# Load_Bank_Master.net
KiCad netlist of a schematic drawn in Altium Designer
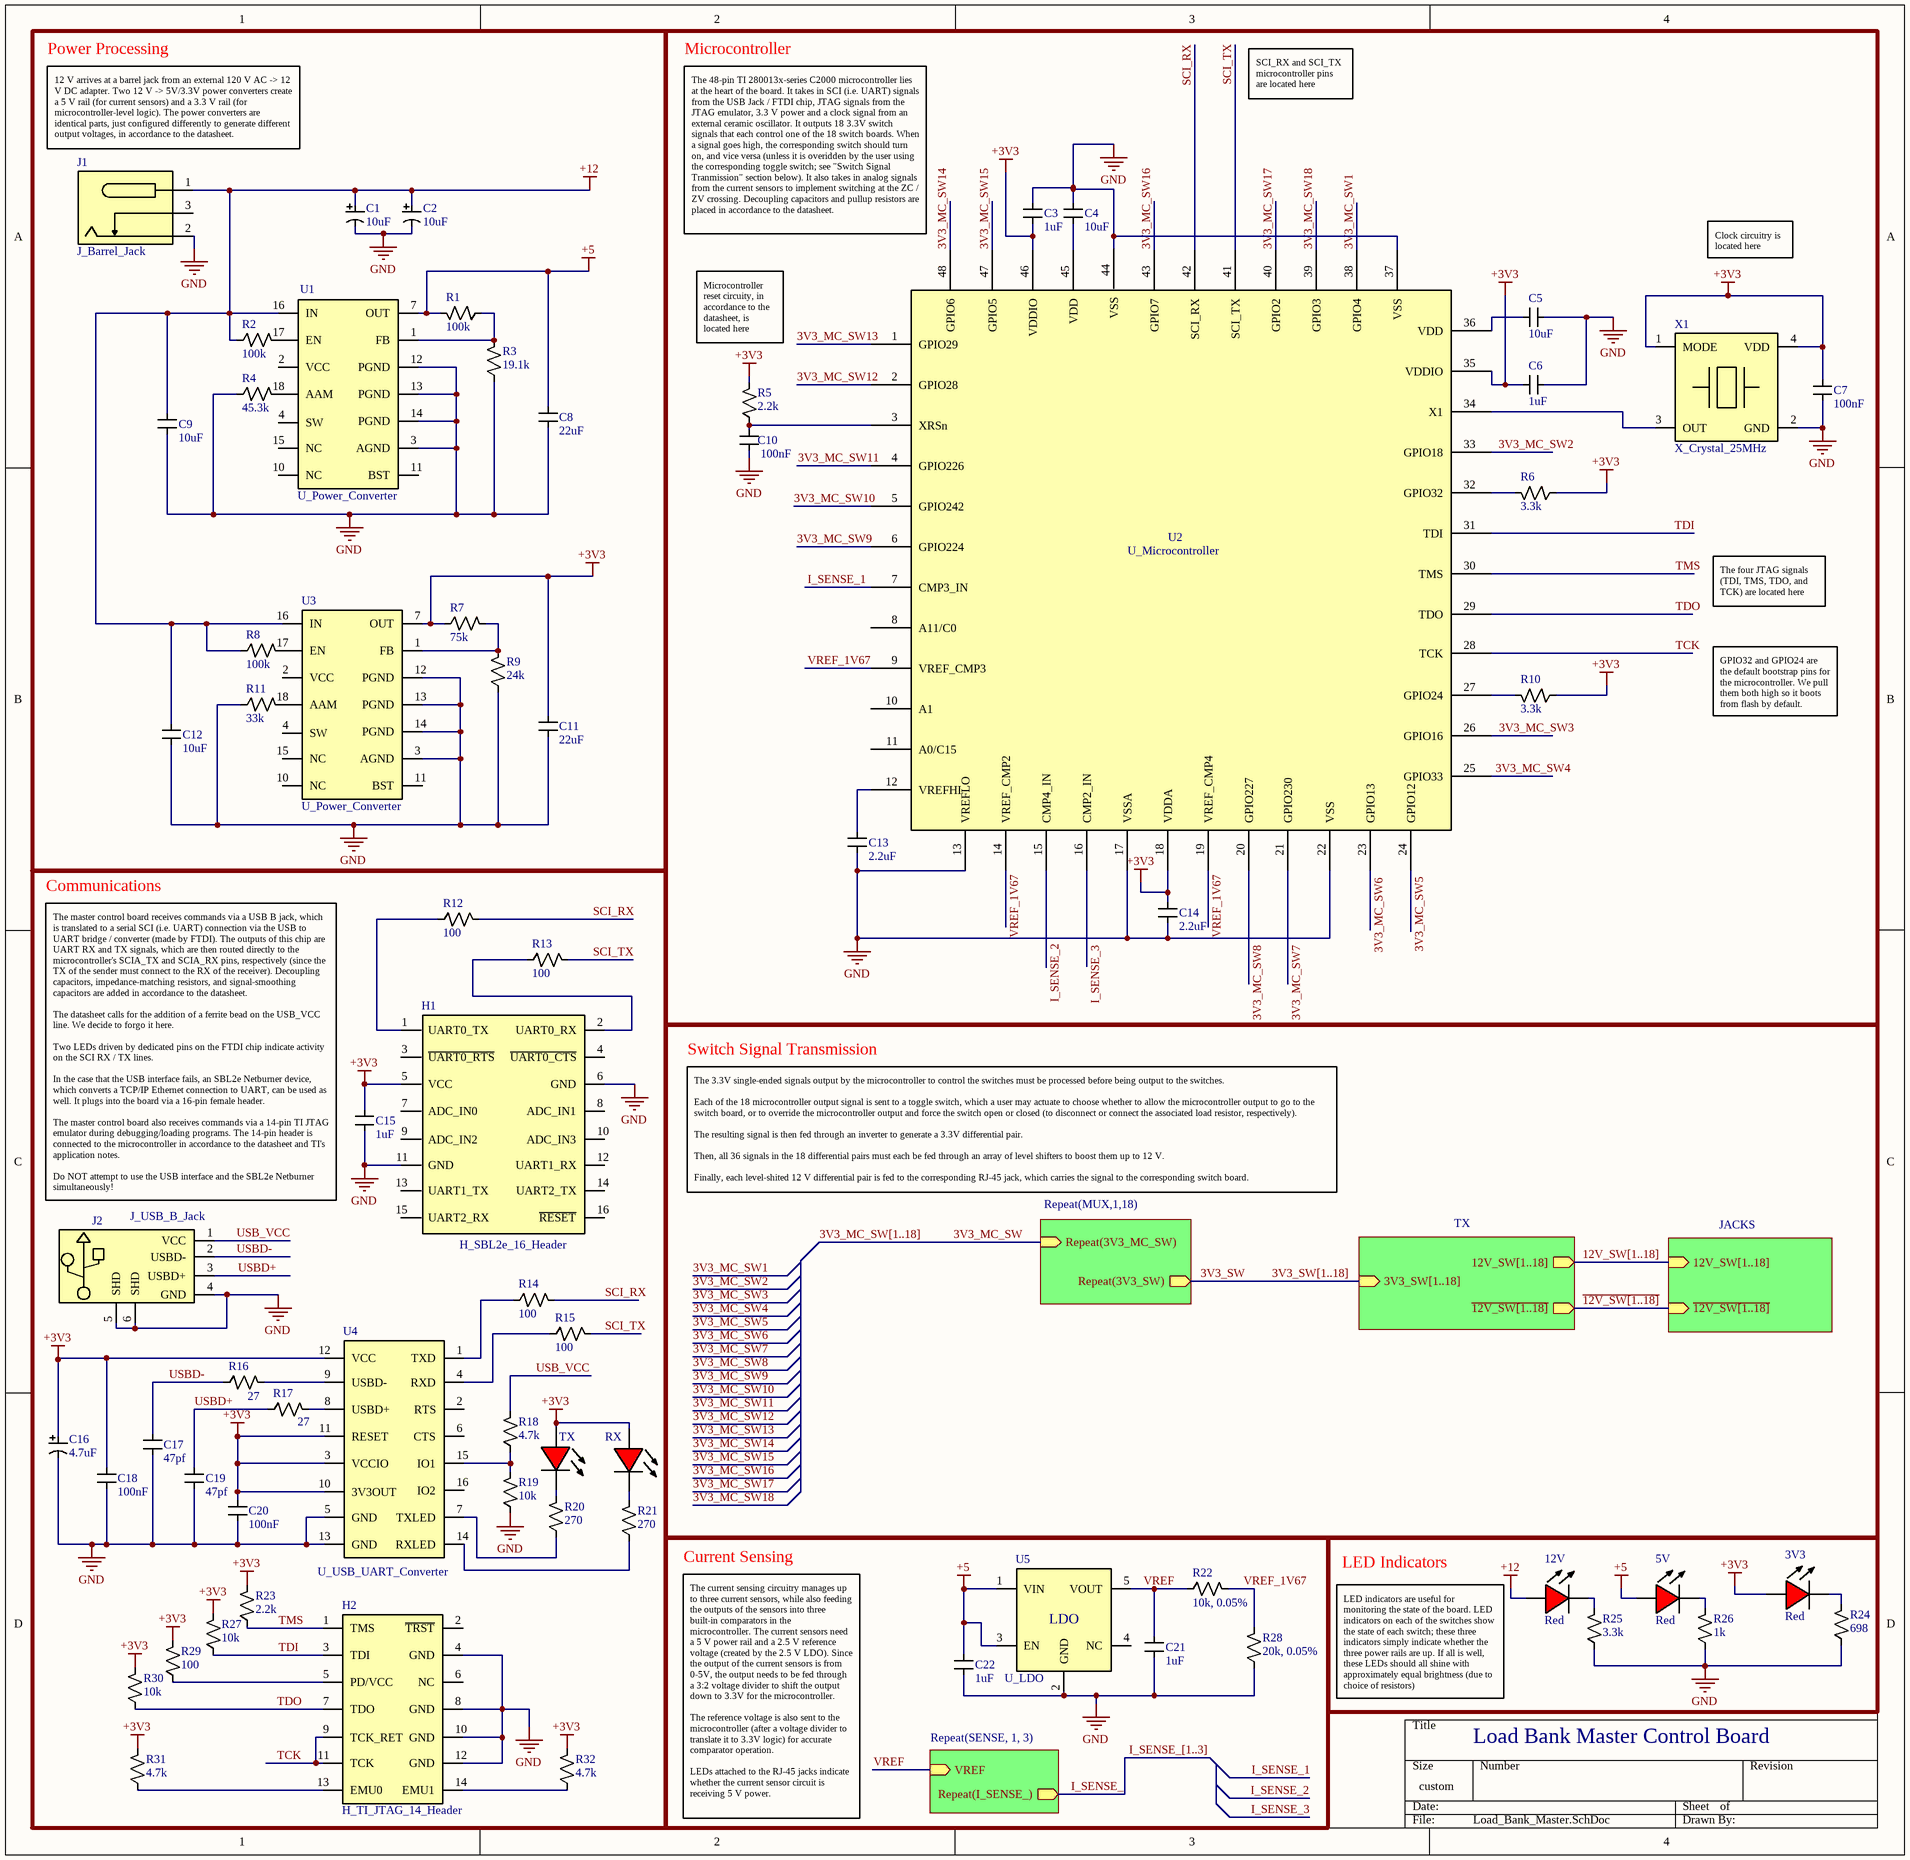
[diagram p0: Load_Bank_Master.SchDoc]

(export (version "E")
  (design (tool "Eeschema 10.0.6"))
  (components
    (comp (ref "3V3")
      (value "Red")
      (footprint "0603_LED")
      (description "LED SMD 0603 Red")
      (libsource (lib "Load_Bank_New_IntLib") (part "LED_0603_Red"))
    )
    (comp (ref "5V")
      (value "Red")
      (footprint "0603_LED")
      (description "LED SMD 0603 Red")
      (libsource (lib "Load_Bank_New_IntLib") (part "LED_0603_Red"))
    )
    (comp (ref "12V")
      (value "Red")
      (footprint "0603_LED")
      (description "LED SMD 0603 Red")
      (libsource (lib "Load_Bank_New_IntLib") (part "LED_0603_Red"))
    )
    (comp (ref "C1")
      (value "10uF")
      (footprint "ALUM_CAP")
      (description "Capacitor SMD Aluminum Electrolytic 10 uF")
      (libsource (lib "Load_Bank_New_IntLib") (part "C_10uF_AlElec"))
    )
    (comp (ref "C2")
      (value "10uF")
      (footprint "ALUM_CAP")
      (description "Capacitor SMD Aluminum Electrolytic 10 uF")
      (libsource (lib "Load_Bank_New_IntLib") (part "C_10uF_AlElec"))
    )
    (comp (ref "C3")
      (value "1uF")
      (footprint "0603_CAP")
      (description "Capacitor SMD MLCC 1 uF 0603 25 V")
      (libsource (lib "Load_Bank_New_IntLib") (part "C_1uF_0603"))
    )
    (comp (ref "C4")
      (value "10uF")
      (footprint "0805_CAP")
      (description "Capacitor SMD MLCC 10 uF 0805")
      (libsource (lib "Load_Bank_New_IntLib") (part "C_10uF_0805"))
    )
    (comp (ref "C5")
      (value "10uF")
      (footprint "0805_CAP")
      (description "Capacitor SMD MLCC 10 uF 0805")
      (libsource (lib "Load_Bank_New_IntLib") (part "C_10uF_0805"))
    )
    (comp (ref "C6")
      (value "1uF")
      (footprint "0603_CAP")
      (description "Capacitor SMD MLCC 1 uF 0603 25 V")
      (libsource (lib "Load_Bank_New_IntLib") (part "C_1uF_0603"))
    )
    (comp (ref "C7")
      (value "100nF")
      (footprint "0603_CAP")
      (description "Capacitor SMD MLCC 100 nF 0603")
      (libsource (lib "Load_Bank_New_IntLib") (part "C_100nF_0603"))
    )
    (comp (ref "C8")
      (value "22uF")
      (footprint "1206_CAP")
      (description "Capacitor SMD MLCC 22 uF 25 V 1206")
      (libsource (lib "Load_Bank_New_IntLib") (part "C_22uF_1206"))
    )
    (comp (ref "C9")
      (value "10uF")
      (footprint "0805_CAP")
      (description "Capacitor SMD MLCC 10 uF 0805")
      (libsource (lib "Load_Bank_New_IntLib") (part "C_10uF_0805"))
    )
    (comp (ref "C10")
      (value "100nF")
      (footprint "0603_CAP")
      (description "Capacitor SMD MLCC 100 nF 0603")
      (libsource (lib "Load_Bank_New_IntLib") (part "C_100nF_0603"))
    )
    (comp (ref "C11")
      (value "22uF")
      (footprint "1206_CAP")
      (description "Capacitor SMD MLCC 22 uF 25 V 1206")
      (libsource (lib "Load_Bank_New_IntLib") (part "C_22uF_1206"))
    )
    (comp (ref "C12")
      (value "10uF")
      (footprint "0805_CAP")
      (description "Capacitor SMD MLCC 10 uF 0805")
      (libsource (lib "Load_Bank_New_IntLib") (part "C_10uF_0805"))
    )
    (comp (ref "C13")
      (value "2.2uF")
      (footprint "0603_CAP")
      (description "Capacitor SMD MLCC 2.2 uF 0603")
      (libsource (lib "Load_Bank_New_IntLib") (part "C_2.2uF_0603"))
    )
    (comp (ref "C14")
      (value "2.2uF")
      (footprint "0603_CAP")
      (description "Capacitor SMD MLCC 2.2 uF 0603")
      (libsource (lib "Load_Bank_New_IntLib") (part "C_2.2uF_0603"))
    )
    (comp (ref "C15")
      (value "1uF")
      (footprint "0603_CAP")
      (description "Capacitor SMD MLCC 1 uF 0603 25 V")
      (libsource (lib "Load_Bank_New_IntLib") (part "C_1uF_0603"))
    )
    (comp (ref "C16")
      (value "4.7uF")
      (footprint "ALUM_CAP")
      (description "Capacitor SMD Aluminum Electrolytic 4.7 uF")
      (libsource (lib "Load_Bank_New_IntLib") (part "C_4.7uF_AlElec"))
    )
    (comp (ref "C17")
      (value "47pf")
      (footprint "0603_CAP")
      (description "Capacitor SMD MLCC 47 pF 0603")
      (libsource (lib "Load_Bank_New_IntLib") (part "C_47pF_0603"))
    )
    (comp (ref "C18")
      (value "100nF")
      (footprint "0603_CAP")
      (description "Capacitor SMD MLCC 100 nF 0603")
      (libsource (lib "Load_Bank_New_IntLib") (part "C_100nF_0603"))
    )
    (comp (ref "C19")
      (value "47pf")
      (footprint "0603_CAP")
      (description "Capacitor SMD MLCC 47 pF 0603")
      (libsource (lib "Load_Bank_New_IntLib") (part "C_47pF_0603"))
    )
    (comp (ref "C20")
      (value "100nF")
      (footprint "0603_CAP")
      (description "Capacitor SMD MLCC 100 nF 0603")
      (libsource (lib "Load_Bank_New_IntLib") (part "C_100nF_0603"))
    )
    (comp (ref "C21")
      (value "1uF")
      (footprint "0603_CAP")
      (description "Capacitor SMD MLCC 1 uF 0603 25 V")
      (libsource (lib "Load_Bank_New_IntLib") (part "C_1uF_0603"))
    )
    (comp (ref "C22")
      (value "1uF")
      (footprint "0603_CAP")
      (description "Capacitor SMD MLCC 1 uF 0603 25 V")
      (libsource (lib "Load_Bank_New_IntLib") (part "C_1uF_0603"))
    )
    (comp (ref "H1")
      (value "H_SBL2e_16_Header")
      (footprint "16PIN_HEADER")
      (description "16-pin SBL2e Netburner Header")
      (libsource (lib "Load_Bank_New_IntLib") (part "H_SBL2e_16_Header"))
    )
    (comp (ref "H2")
      (value "H_TI_JTAG_14_Header")
      (footprint "14PIN_HEADER")
      (description "14-pin TI JTAG Header")
      (libsource (lib "Load_Bank_New_IntLib") (part "H_TI_JTAG_14_Header"))
    )
    (comp (ref "J1")
      (value "J_Barrel_Jack")
      (footprint "PWR_JACK")
      (description "Jack 12 V Barrel Jack Power Plug")
      (libsource (lib "Load_Bank_New_IntLib") (part "J_Barrel_Jack"))
    )
    (comp (ref "J2")
      (value "J_USB_B_Jack")
      (footprint "USB_B_JACK")
      (description "Jack USB Type B")
      (libsource (lib "Load_Bank_New_IntLib") (part "J_USB_B_Jack"))
    )
    (comp (ref "R1")
      (value "100k")
      (footprint "0603_RES")
      (description "Resistor 100 kOhm 0603 0.5%")
      (libsource (lib "Load_Bank_New_IntLib") (part "R_100kOhm_0603_0.5%"))
    )
    (comp (ref "R2")
      (value "100k")
      (footprint "0603_RES")
      (description "Resistor 100 kOhm 0603 0.5%")
      (libsource (lib "Load_Bank_New_IntLib") (part "R_100kOhm_0603_0.5%"))
    )
    (comp (ref "R3")
      (value "19.1k")
      (footprint "0603_RES")
      (description "Resistor 19.1 kOhm 0603 0.5%")
      (libsource (lib "Load_Bank_New_IntLib") (part "R_19.1kOhm_0603_0.5%"))
    )
    (comp (ref "R4")
      (value "45.3k")
      (footprint "0603_RES")
      (description "Resistor 45.3 kOhm 0603 0.5%")
      (libsource (lib "Load_Bank_New_IntLib") (part "R_45.3kOhm_0603_0.5%"))
    )
    (comp (ref "R5")
      (value "2.2k")
      (footprint "0603_RES")
      (description "Resistor 2.2 kOhm 0603 0.5%")
      (libsource (lib "Load_Bank_New_IntLib") (part "R_2.2kOhm_0603_0.5%"))
    )
    (comp (ref "R6")
      (value "3.3k")
      (footprint "0603_RES")
      (description "Resistor 3.3 kOhm 0603 1%")
      (libsource (lib "Load_Bank_New_IntLib") (part "R_3300Ohm_0603_1%"))
    )
    (comp (ref "R7")
      (value "75k")
      (footprint "0603_RES")
      (description "Resistor 75 kOhm 0603 0.5%")
      (libsource (lib "Load_Bank_New_IntLib") (part "R_75kOhm_0603_0.5%"))
    )
    (comp (ref "R8")
      (value "100k")
      (footprint "0603_RES")
      (description "Resistor 100 kOhm 0603 0.5%")
      (libsource (lib "Load_Bank_New_IntLib") (part "R_100kOhm_0603_0.5%"))
    )
    (comp (ref "R9")
      (value "24k")
      (footprint "0603_RES")
      (description "Resistor 24 kOhm 0603 0.5%")
      (libsource (lib "Load_Bank_New_IntLib") (part "R_24kOhm_0603_0.5%"))
    )
    (comp (ref "R10")
      (value "3.3k")
      (footprint "0603_RES")
      (description "Resistor 3.3 kOhm 0603 1%")
      (libsource (lib "Load_Bank_New_IntLib") (part "R_3300Ohm_0603_1%"))
    )
    (comp (ref "R11")
      (value "33k")
      (footprint "0603_RES")
      (description "Resistor 33 kOhm 0603 0.5%")
      (libsource (lib "Load_Bank_New_IntLib") (part "R_33kOhm_0603_0.5%"))
    )
    (comp (ref "R12")
      (value "100")
      (footprint "0603_RES")
      (description "Resistor 100 Ohm 0603 0.5%")
      (libsource (lib "Load_Bank_New_IntLib") (part "R_100Ohm_0603_0.5%"))
    )
    (comp (ref "R13")
      (value "100")
      (footprint "0603_RES")
      (description "Resistor 100 Ohm 0603 0.5%")
      (libsource (lib "Load_Bank_New_IntLib") (part "R_100Ohm_0603_0.5%"))
    )
    (comp (ref "R14")
      (value "100")
      (footprint "0603_RES")
      (description "Resistor 100 Ohm 0603 0.5%")
      (libsource (lib "Load_Bank_New_IntLib") (part "R_100Ohm_0603_0.5%"))
    )
    (comp (ref "R15")
      (value "100")
      (footprint "0603_RES")
      (description "Resistor 100 Ohm 0603 0.5%")
      (libsource (lib "Load_Bank_New_IntLib") (part "R_100Ohm_0603_0.5%"))
    )
    (comp (ref "R16")
      (value "27")
      (footprint "0603_RES")
      (description "Resistor 27 Ohm 0603 1%")
      (libsource (lib "Load_Bank_New_IntLib") (part "R_27Ohm_0603_1%"))
    )
    (comp (ref "R17")
      (value "27")
      (footprint "0603_RES")
      (description "Resistor 27 Ohm 0603 1%")
      (libsource (lib "Load_Bank_New_IntLib") (part "R_27Ohm_0603_1%"))
    )
    (comp (ref "R18")
      (value "4.7k")
      (footprint "0603_RES")
      (description "Resistor 4.7k kOhm 0603 0.5%")
      (libsource (lib "Load_Bank_New_IntLib") (part "R_4.7kOhm_0603_0.5%_1"))
    )
    (comp (ref "R19")
      (value "10k")
      (footprint "0603_RES")
      (description "Resistor 10 kOhm 0603 0.5%")
      (libsource (lib "Load_Bank_New_IntLib") (part "R_10kOhm_0603_0.5%"))
    )
    (comp (ref "R20")
      (value "270")
      (footprint "0603_RES")
      (description "Resistor 270 Ohm 0603 1%")
      (libsource (lib "Load_Bank_New_IntLib") (part "R_270Ohm_0603_1%"))
    )
    (comp (ref "R21")
      (value "270")
      (footprint "0603_RES")
      (description "Resistor 270 Ohm 0603 1%")
      (libsource (lib "Load_Bank_New_IntLib") (part "R_270Ohm_0603_1%"))
    )
    (comp (ref "R22")
      (value "10k, 0.05%")
      (footprint "0603_RES")
      (description "Resistor 10 kOhm 0603 0.05%")
      (libsource (lib "Load_Bank_New_IntLib") (part "R_10kOhm_0603_0.05%"))
    )
    (comp (ref "R23")
      (value "2.2k")
      (footprint "0603_RES")
      (description "Resistor 2.2 kOhm 0603 0.5%")
      (libsource (lib "Load_Bank_New_IntLib") (part "R_2.2kOhm_0603_0.5%"))
    )
    (comp (ref "R24")
      (value "698")
      (footprint "0603_RES")
      (description "Resistor 698 Ohm 0603 0.5%")
      (libsource (lib "Load_Bank_New_IntLib") (part "R_698Ohm_0603_0.5%"))
    )
    (comp (ref "R25")
      (value "3.3k")
      (footprint "0603_RES")
      (description "Resistor 3.3 kOhm 0603 1%")
      (libsource (lib "Load_Bank_New_IntLib") (part "R_3300Ohm_0603_1%"))
    )
    (comp (ref "R26")
      (value "1k")
      (footprint "0603_RES")
      (description "Resistor 1 kOhm 0603 0.5%")
      (libsource (lib "Load_Bank_New_IntLib") (part "R_1kOhm_0603_0.5%"))
    )
    (comp (ref "R27")
      (value "10k")
      (footprint "0603_RES")
      (description "Resistor 10 kOhm 0603 0.5%")
      (libsource (lib "Load_Bank_New_IntLib") (part "R_10kOhm_0603_0.5%"))
    )
    (comp (ref "R28")
      (value "20k, 0.05%")
      (footprint "0603_RES")
      (description "Resistor 20 kOhm 0603 0.05%")
      (libsource (lib "Load_Bank_New_IntLib") (part "R_20kOhm_0603_0.05%"))
    )
    (comp (ref "R29")
      (value "100")
      (footprint "0603_RES")
      (description "Resistor 100 Ohm 0603 0.5%")
      (libsource (lib "Load_Bank_New_IntLib") (part "R_100Ohm_0603_0.5%"))
    )
    (comp (ref "R30")
      (value "10k")
      (footprint "0603_RES")
      (description "Resistor 10 kOhm 0603 0.5%")
      (libsource (lib "Load_Bank_New_IntLib") (part "R_10kOhm_0603_0.5%"))
    )
    (comp (ref "R31")
      (value "4.7k")
      (footprint "0603_RES")
      (description "Resistor 4.7k kOhm 0603 0.5%")
      (libsource (lib "Load_Bank_New_IntLib") (part "R_4.7kOhm_0603_0.5%_1"))
    )
    (comp (ref "R32")
      (value "4.7k")
      (footprint "0603_RES")
      (description "Resistor 4.7k kOhm 0603 0.5%")
      (libsource (lib "Load_Bank_New_IntLib") (part "R_4.7kOhm_0603_0.5%_1"))
    )
    (comp (ref "RX")
      (value "Red")
      (footprint "0603_LED")
      (description "LED SMD 0603 Red")
      (libsource (lib "Load_Bank_New_IntLib") (part "LED_0603_Red"))
    )
    (comp (ref "TX")
      (value "Red")
      (footprint "0603_LED")
      (description "LED SMD 0603 Red")
      (libsource (lib "Load_Bank_New_IntLib") (part "LED_0603_Red"))
    )
    (comp (ref "U1")
      (value "U_Power_Converter")
      (footprint "PWR_CONVERTER")
      (description "IC 12 V to 5V/3.3V switching power converter")
      (libsource (lib "Load_Bank_New_IntLib") (part "U_Power_Converter"))
    )
    (comp (ref "U2")
      (value "U_Microcontroller")
      (footprint "MICROCONTROLLER")
      (description "IC TI C2000 Microcontroller, 48-pin LQFP")
      (libsource (lib "Load_Bank_New_IntLib") (part "U_Microcontroller"))
    )
    (comp (ref "U3")
      (value "U_Power_Converter")
      (footprint "PWR_CONVERTER")
      (description "IC 12 V to 5V/3.3V switching power converter")
      (libsource (lib "Load_Bank_New_IntLib") (part "U_Power_Converter"))
    )
    (comp (ref "U4")
      (value "U_USB_UART_Converter")
      (footprint "TSSOP-16")
      (description "FTDI USB to UART Converter TSSOP-16 FT230-XS")
      (libsource (lib "Load_Bank_New_IntLib") (part "U_USB_UART_Converter"))
    )
    (comp (ref "U5")
      (value "U_LDO")
      (footprint "SOT25")
      (description "IC 2.5 V LDO")
      (libsource (lib "Load_Bank_New_IntLib") (part "U_LDO"))
    )
    (comp (ref "X1")
      (value "X_Crystal_25MHz")
      (footprint "CRYSTAL")
      (description "Crystal Oscillator 25 MHz 3.3 V")
      (libsource (lib "Load_Bank_New_IntLib") (part "X_Crystal_25MHz"))
    )
  )
  (nets
    (net (code "37") (name "+3V3") (class "Default")
      (node (ref "3V3") (pin "2") (pintype "passive"))
      (node (ref "C11") (pin "2") (pintype "passive"))
      (node (ref "C14") (pin "2") (pintype "passive"))
      (node (ref "C15") (pin "2") (pintype "passive"))
      (node (ref "C16") (pin "2") (pintype "passive"))
      (node (ref "C18") (pin "2") (pintype "passive"))
      (node (ref "C20") (pin "2") (pintype "passive"))
      (node (ref "C3") (pin "1") (pintype "passive"))
      (node (ref "C6") (pin "1") (pintype "passive"))
      (node (ref "C7") (pin "2") (pintype "passive"))
      (node (ref "H1") (pin "5") (pinfunction "VCC_5") (pintype "passive"))
      (node (ref "R10") (pin "1") (pintype "passive"))
      (node (ref "R23") (pin "2") (pintype "passive"))
      (node (ref "R27") (pin "2") (pintype "passive"))
      (node (ref "R29") (pin "2") (pintype "passive"))
      (node (ref "R30") (pin "2") (pintype "passive"))
      (node (ref "R31") (pin "2") (pintype "passive"))
      (node (ref "R32") (pin "2") (pintype "passive"))
      (node (ref "R5") (pin "2") (pintype "passive"))
      (node (ref "R6") (pin "1") (pintype "passive"))
      (node (ref "R7") (pin "1") (pintype "passive"))
      (node (ref "RX") (pin "2") (pintype "passive"))
      (node (ref "TX") (pin "2") (pintype "passive"))
      (node (ref "U2") (pin "18") (pinfunction "VDDA_18") (pintype "passive"))
      (node (ref "U2") (pin "35") (pinfunction "VDDIO_35") (pintype "passive"))
      (node (ref "U2") (pin "46") (pinfunction "VDDIO_46") (pintype "passive"))
      (node (ref "U3") (pin "7") (pinfunction "OUT_7") (pintype "passive"))
      (node (ref "U4") (pin "10") (pinfunction "3V3OUT_10") (pintype "passive"))
      (node (ref "U4") (pin "11") (pinfunction "RESET_11") (pintype "passive"))
      (node (ref "U4") (pin "12") (pinfunction "VCC_12") (pintype "passive"))
      (node (ref "U4") (pin "3") (pinfunction "VCCIO_3") (pintype "passive"))
      (node (ref "X1") (pin "1") (pinfunction "MODE_1") (pintype "passive"))
      (node (ref "X1") (pin "4") (pinfunction "VDD_4") (pintype "passive"))
    )
    (net (code "38") (name "+5") (class "Default")
      (node (ref "5V") (pin "2") (pintype "passive"))
      (node (ref "C22") (pin "2") (pintype "passive"))
      (node (ref "C8") (pin "2") (pintype "passive"))
      (node (ref "R1") (pin "2") (pintype "passive"))
      (node (ref "U1") (pin "7") (pinfunction "OUT_7") (pintype "passive"))
      (node (ref "U5") (pin "1") (pinfunction "VIN_1") (pintype "passive"))
      (node (ref "U5") (pin "3") (pinfunction "EN_3") (pintype "passive"))
    )
    (net (code "39") (name "+12") (class "Default")
      (node (ref "12V") (pin "2") (pintype "passive"))
      (node (ref "C1") (pin "2") (pintype "passive"))
      (node (ref "C12") (pin "2") (pintype "passive"))
      (node (ref "C2") (pin "2") (pintype "passive"))
      (node (ref "C9") (pin "2") (pintype "passive"))
      (node (ref "J1") (pin "1") (pinfunction "GND_1") (pintype "passive"))
      (node (ref "R2") (pin "1") (pintype "passive"))
      (node (ref "R8") (pin "1") (pintype "passive"))
      (node (ref "U1") (pin "16") (pinfunction "IN_16") (pintype "passive"))
      (node (ref "U3") (pin "16") (pinfunction "IN_16") (pintype "passive"))
    )
    (net (code "41") (name "/3V3_MC_SW1") (class "Default")
      (node (ref "U2") (pin "38") (pinfunction "GPIO4_38") (pintype "passive"))
    )
    (net (code "42") (name "/3V3_MC_SW2") (class "Default")
      (node (ref "U2") (pin "33") (pinfunction "GPIO18_33") (pintype "passive"))
    )
    (net (code "43") (name "/3V3_MC_SW3") (class "Default")
      (node (ref "U2") (pin "26") (pinfunction "GPIO16_26") (pintype "passive"))
    )
    (net (code "44") (name "/3V3_MC_SW4") (class "Default")
      (node (ref "U2") (pin "25") (pinfunction "GPIO33_25") (pintype "passive"))
    )
    (net (code "45") (name "/3V3_MC_SW5") (class "Default")
      (node (ref "U2") (pin "24") (pinfunction "GPIO12_24") (pintype "passive"))
    )
    (net (code "46") (name "/3V3_MC_SW6") (class "Default")
      (node (ref "U2") (pin "23") (pinfunction "GPIO13_23") (pintype "passive"))
    )
    (net (code "47") (name "/3V3_MC_SW7") (class "Default")
      (node (ref "U2") (pin "21") (pinfunction "GPIO230_21") (pintype "passive"))
    )
    (net (code "48") (name "/3V3_MC_SW8") (class "Default")
      (node (ref "U2") (pin "20") (pinfunction "GPIO227_20") (pintype "passive"))
    )
    (net (code "49") (name "/3V3_MC_SW9") (class "Default")
      (node (ref "U2") (pin "6") (pinfunction "GPIO224_6") (pintype "passive"))
    )
    (net (code "50") (name "/3V3_MC_SW10") (class "Default")
      (node (ref "U2") (pin "5") (pinfunction "GPIO242_5") (pintype "passive"))
    )
    (net (code "51") (name "/3V3_MC_SW11") (class "Default")
      (node (ref "U2") (pin "4") (pinfunction "GPIO226_4") (pintype "passive"))
    )
    (net (code "52") (name "/3V3_MC_SW12") (class "Default")
      (node (ref "U2") (pin "2") (pinfunction "GPIO28_2") (pintype "passive"))
    )
    (net (code "53") (name "/3V3_MC_SW13") (class "Default")
      (node (ref "U2") (pin "1") (pinfunction "GPIO29_1") (pintype "passive"))
    )
    (net (code "54") (name "/3V3_MC_SW14") (class "Default")
      (node (ref "U2") (pin "48") (pinfunction "GPIO6_48") (pintype "passive"))
    )
    (net (code "55") (name "/3V3_MC_SW15") (class "Default")
      (node (ref "U2") (pin "47") (pinfunction "GPIO5_47") (pintype "passive"))
    )
    (net (code "56") (name "/3V3_MC_SW16") (class "Default")
      (node (ref "U2") (pin "43") (pinfunction "GPIO7_43") (pintype "passive"))
    )
    (net (code "57") (name "/3V3_MC_SW17") (class "Default")
      (node (ref "U2") (pin "40") (pinfunction "GPIO2_40") (pintype "passive"))
    )
    (net (code "58") (name "/3V3_MC_SW18") (class "Default")
      (node (ref "U2") (pin "39") (pinfunction "GPIO3_39") (pintype "passive"))
    )
    (net (code "64") (name "/I_SENSE_1") (class "Default")
      (node (ref "U2") (pin "7") (pinfunction "CMP3_IN_7") (pintype "passive"))
    )
    (net (code "65") (name "/I_SENSE_2") (class "Default")
      (node (ref "U2") (pin "15") (pinfunction "CMP4_IN_15") (pintype "passive"))
    )
    (net (code "66") (name "/I_SENSE_3") (class "Default")
      (node (ref "U2") (pin "16") (pinfunction "CMP2_IN_16") (pintype "passive"))
    )
    (net (code "68") (name "/SCI_RX") (class "Default")
      (node (ref "R12") (pin "2") (pintype "passive"))
      (node (ref "R14") (pin "2") (pintype "passive"))
      (node (ref "U2") (pin "42") (pinfunction "SCI_RX_42") (pintype "passive"))
    )
    (net (code "69") (name "/SCI_TX") (class "Default")
      (node (ref "R13") (pin "2") (pintype "passive"))
      (node (ref "R15") (pin "2") (pintype "passive"))
      (node (ref "U2") (pin "41") (pinfunction "SCI_TX_41") (pintype "passive"))
    )
    (net (code "70") (name "/TCK") (class "Default")
      (node (ref "H2") (pin "11") (pinfunction "TCK_11") (pintype "passive"))
      (node (ref "H2") (pin "9") (pinfunction "TCK_RET_9") (pintype "passive"))
      (node (ref "U2") (pin "28") (pinfunction "TCK_28") (pintype "passive"))
    )
    (net (code "71") (name "/TDI") (class "Default")
      (node (ref "H2") (pin "3") (pinfunction "TDI_3") (pintype "passive"))
      (node (ref "R27") (pin "1") (pintype "passive"))
      (node (ref "U2") (pin "31") (pinfunction "TDI_31") (pintype "passive"))
    )
    (net (code "72") (name "/TDO") (class "Default")
      (node (ref "H2") (pin "7") (pinfunction "TDO_7") (pintype "passive"))
      (node (ref "R30") (pin "1") (pintype "passive"))
      (node (ref "U2") (pin "29") (pinfunction "TDO_29") (pintype "passive"))
    )
    (net (code "73") (name "/TMS") (class "Default")
      (node (ref "H2") (pin "1") (pinfunction "TMS_1") (pintype "passive"))
      (node (ref "R23") (pin "1") (pintype "passive"))
      (node (ref "U2") (pin "30") (pinfunction "TMS_30") (pintype "passive"))
    )
    (net (code "74") (name "/USBD+") (class "Default")
      (node (ref "C19") (pin "2") (pintype "passive"))
      (node (ref "J2") (pin "3") (pinfunction "USBD+_3") (pintype "passive"))
      (node (ref "R17") (pin "1") (pintype "passive"))
    )
    (net (code "75") (name "/USBD-") (class "Default")
      (node (ref "C17") (pin "2") (pintype "passive"))
      (node (ref "J2") (pin "2") (pinfunction "USBD-_2") (pintype "passive"))
      (node (ref "R16") (pin "1") (pintype "passive"))
    )
    (net (code "76") (name "/USB_VCC") (class "Default")
      (node (ref "J2") (pin "1") (pinfunction "VCC_1") (pintype "passive"))
      (node (ref "R18") (pin "2") (pintype "passive"))
    )
    (net (code "77") (name "/VREF") (class "Default")
      (node (ref "C21") (pin "2") (pintype "passive"))
      (node (ref "R22") (pin "1") (pintype "passive"))
      (node (ref "U5") (pin "5") (pinfunction "VOUT_5") (pintype "passive"))
    )
    (net (code "78") (name "/VREF_1V67") (class "Default")
      (node (ref "R22") (pin "2") (pintype "passive"))
      (node (ref "R28") (pin "2") (pintype "passive"))
      (node (ref "U2") (pin "14") (pinfunction "VREF_CMP2_14") (pintype "passive"))
      (node (ref "U2") (pin "19") (pinfunction "VREF_CMP4_19") (pintype "passive"))
      (node (ref "U2") (pin "9") (pinfunction "VREF_CMP3_9") (pintype "passive"))
    )
    (net (code "79") (name "GND") (class "Default")
      (node (ref "C1") (pin "1") (pintype "passive"))
      (node (ref "C10") (pin "1") (pintype "passive"))
      (node (ref "C11") (pin "1") (pintype "passive"))
      (node (ref "C12") (pin "1") (pintype "passive"))
      (node (ref "C13") (pin "1") (pintype "passive"))
      (node (ref "C14") (pin "1") (pintype "passive"))
      (node (ref "C15") (pin "1") (pintype "passive"))
      (node (ref "C16") (pin "1") (pintype "passive"))
      (node (ref "C17") (pin "1") (pintype "passive"))
      (node (ref "C18") (pin "1") (pintype "passive"))
      (node (ref "C19") (pin "1") (pintype "passive"))
      (node (ref "C2") (pin "1") (pintype "passive"))
      (node (ref "C20") (pin "1") (pintype "passive"))
      (node (ref "C21") (pin "1") (pintype "passive"))
      (node (ref "C22") (pin "1") (pintype "passive"))
      (node (ref "C3") (pin "2") (pintype "passive"))
      (node (ref "C4") (pin "2") (pintype "passive"))
      (node (ref "C5") (pin "2") (pintype "passive"))
      (node (ref "C6") (pin "2") (pintype "passive"))
      (node (ref "C7") (pin "1") (pintype "passive"))
      (node (ref "C8") (pin "1") (pintype "passive"))
      (node (ref "C9") (pin "1") (pintype "passive"))
      (node (ref "H1") (pin "11") (pinfunction "GND_11") (pintype "passive"))
      (node (ref "H1") (pin "6") (pinfunction "GND_6") (pintype "passive"))
      (node (ref "H2") (pin "10") (pinfunction "GND_10") (pintype "passive"))
      (node (ref "H2") (pin "12") (pinfunction "GND_12") (pintype "passive"))
      (node (ref "H2") (pin "4") (pinfunction "GND_4") (pintype "passive"))
      (node (ref "H2") (pin "8") (pinfunction "GND_8") (pintype "passive"))
      (node (ref "J1") (pin "2") (pinfunction "PWR_JACK_2") (pintype "passive"))
      (node (ref "J2") (pin "4") (pinfunction "GND_4") (pintype "passive"))
      (node (ref "J2") (pin "5") (pinfunction "SHD_5") (pintype "passive"))
      (node (ref "J2") (pin "6") (pinfunction "SHD_6") (pintype "passive"))
      (node (ref "R11") (pin "1") (pintype "passive"))
      (node (ref "R19") (pin "1") (pintype "passive"))
      (node (ref "R24") (pin "1") (pintype "passive"))
      (node (ref "R25") (pin "1") (pintype "passive"))
      (node (ref "R26") (pin "1") (pintype "passive"))
      (node (ref "R28") (pin "1") (pintype "passive"))
      (node (ref "R3") (pin "1") (pintype "passive"))
      (node (ref "R4") (pin "1") (pintype "passive"))
      (node (ref "R9") (pin "1") (pintype "passive"))
      (node (ref "U1") (pin "12") (pinfunction "PGND_12") (pintype "passive"))
      (node (ref "U1") (pin "13") (pinfunction "PGND_13") (pintype "passive"))
      (node (ref "U1") (pin "14") (pinfunction "PGND_14") (pintype "passive"))
      (node (ref "U1") (pin "3") (pinfunction "AGND_3") (pintype "passive"))
      (node (ref "U2") (pin "13") (pinfunction "VREFLO_13") (pintype "passive"))
      (node (ref "U2") (pin "17") (pinfunction "VSSA_17") (pintype "passive"))
      (node (ref "U2") (pin "22") (pinfunction "VSS_22") (pintype "passive"))
      (node (ref "U2") (pin "37") (pinfunction "VSS_37") (pintype "passive"))
      (node (ref "U2") (pin "44") (pinfunction "VSS_44") (pintype "passive"))
      (node (ref "U3") (pin "12") (pinfunction "PGND_12") (pintype "passive"))
      (node (ref "U3") (pin "13") (pinfunction "PGND_13") (pintype "passive"))
      (node (ref "U3") (pin "14") (pinfunction "PGND_14") (pintype "passive"))
      (node (ref "U3") (pin "3") (pinfunction "AGND_3") (pintype "passive"))
      (node (ref "U4") (pin "13") (pinfunction "GND_13") (pintype "passive"))
      (node (ref "U4") (pin "5") (pinfunction "GND_5") (pintype "passive"))
      (node (ref "U5") (pin "2") (pinfunction "GND_2") (pintype "passive"))
      (node (ref "X1") (pin "2") (pinfunction "GND_2") (pintype "passive"))
    )
    (net (code "80") (name "Net-(3V3-Pad1)") (class "Default")
      (node (ref "3V3") (pin "1") (pintype "passive"))
      (node (ref "R24") (pin "2") (pintype "passive"))
    )
    (net (code "81") (name "Net-(5V-Pad1)") (class "Default")
      (node (ref "5V") (pin "1") (pintype "passive"))
      (node (ref "R26") (pin "2") (pintype "passive"))
    )
    (net (code "82") (name "Net-(12V-Pad1)") (class "Default")
      (node (ref "12V") (pin "1") (pintype "passive"))
      (node (ref "R25") (pin "2") (pintype "passive"))
    )
    (net (code "83") (name "Net-(C4-Pad1)") (class "Default")
      (node (ref "C4") (pin "1") (pintype "passive"))
      (node (ref "U2") (pin "45") (pinfunction "VDD_45") (pintype "passive"))
    )
    (net (code "84") (name "Net-(C5-Pad1)") (class "Default")
      (node (ref "C5") (pin "1") (pintype "passive"))
      (node (ref "U2") (pin "36") (pinfunction "VDD_36") (pintype "passive"))
    )
    (net (code "85") (name "Net-(H1-UART0_RX)") (class "Default")
      (node (ref "H1") (pin "2") (pinfunction "UART0_RX_2") (pintype "passive"))
      (node (ref "R13") (pin "1") (pintype "passive"))
    )
    (net (code "86") (name "Net-(H1-UART0_TX)") (class "Default")
      (node (ref "H1") (pin "1") (pinfunction "UART0_TX_1") (pintype "passive"))
      (node (ref "R12") (pin "1") (pintype "passive"))
    )
    (net (code "87") (name "Net-(H2-EMU0)") (class "Default")
      (node (ref "H2") (pin "13") (pinfunction "EMU0_13") (pintype "passive"))
      (node (ref "R31") (pin "1") (pintype "passive"))
    )
    (net (code "88") (name "Net-(H2-EMU1)") (class "Default")
      (node (ref "H2") (pin "14") (pinfunction "EMU1_14") (pintype "passive"))
      (node (ref "R32") (pin "1") (pintype "passive"))
    )
    (net (code "89") (name "Net-(H2-PD{slash}VCC)") (class "Default")
      (node (ref "H2") (pin "5") (pinfunction "PD/VCC_5") (pintype "passive"))
      (node (ref "R29") (pin "1") (pintype "passive"))
    )
    (net (code "90") (name "Net-(R20-Pad2)") (class "Default")
      (node (ref "R20") (pin "2") (pintype "passive"))
      (node (ref "TX") (pin "1") (pintype "passive"))
    )
    (net (code "91") (name "Net-(R21-Pad2)") (class "Default")
      (node (ref "R21") (pin "2") (pintype "passive"))
      (node (ref "RX") (pin "1") (pintype "passive"))
    )
    (net (code "92") (name "Net-(U1-AAM)") (class "Default")
      (node (ref "R4") (pin "2") (pintype "passive"))
      (node (ref "U1") (pin "18") (pinfunction "AAM_18") (pintype "passive"))
    )
    (net (code "93") (name "Net-(U1-EN)") (class "Default")
      (node (ref "R2") (pin "2") (pintype "passive"))
      (node (ref "U1") (pin "17") (pinfunction "EN_17") (pintype "passive"))
    )
    (net (code "94") (name "Net-(U1-FB)") (class "Default")
      (node (ref "R1") (pin "1") (pintype "passive"))
      (node (ref "R3") (pin "2") (pintype "passive"))
      (node (ref "U1") (pin "1") (pinfunction "FB_1") (pintype "passive"))
    )
    (net (code "95") (name "Net-(U2-GPIO24)") (class "Default")
      (node (ref "R10") (pin "2") (pintype "passive"))
      (node (ref "U2") (pin "27") (pinfunction "GPIO24_27") (pintype "passive"))
    )
    (net (code "96") (name "Net-(U2-GPIO32)") (class "Default")
      (node (ref "R6") (pin "2") (pintype "passive"))
      (node (ref "U2") (pin "32") (pinfunction "GPIO32_32") (pintype "passive"))
    )
    (net (code "97") (name "Net-(U2-VREFHI)") (class "Default")
      (node (ref "C13") (pin "2") (pintype "passive"))
      (node (ref "U2") (pin "12") (pinfunction "VREFHI_12") (pintype "passive"))
    )
    (net (code "98") (name "Net-(U2-X1)") (class "Default")
      (node (ref "U2") (pin "34") (pinfunction "X1_34") (pintype "passive"))
      (node (ref "X1") (pin "3") (pinfunction "OUT_3") (pintype "passive"))
    )
    (net (code "99") (name "Net-(U2-XRSn)") (class "Default")
      (node (ref "C10") (pin "2") (pintype "passive"))
      (node (ref "R5") (pin "1") (pintype "passive"))
      (node (ref "U2") (pin "3") (pinfunction "XRSn_3") (pintype "passive"))
    )
    (net (code "100") (name "Net-(U3-AAM)") (class "Default")
      (node (ref "R11") (pin "2") (pintype "passive"))
      (node (ref "U3") (pin "18") (pinfunction "AAM_18") (pintype "passive"))
    )
    (net (code "101") (name "Net-(U3-EN)") (class "Default")
      (node (ref "R8") (pin "2") (pintype "passive"))
      (node (ref "U3") (pin "17") (pinfunction "EN_17") (pintype "passive"))
    )
    (net (code "102") (name "Net-(U3-FB)") (class "Default")
      (node (ref "R7") (pin "2") (pintype "passive"))
      (node (ref "R9") (pin "2") (pintype "passive"))
      (node (ref "U3") (pin "1") (pinfunction "FB_1") (pintype "passive"))
    )
    (net (code "103") (name "Net-(U4-IO1)") (class "Default")
      (node (ref "R18") (pin "1") (pintype "passive"))
      (node (ref "R19") (pin "2") (pintype "passive"))
      (node (ref "U4") (pin "15") (pinfunction "IO1_15") (pintype "passive"))
    )
    (net (code "104") (name "Net-(U4-RXD)") (class "Default")
      (node (ref "R15") (pin "1") (pintype "passive"))
      (node (ref "U4") (pin "4") (pinfunction "RXD_4") (pintype "passive"))
    )
    (net (code "105") (name "Net-(U4-RXLED)") (class "Default")
      (node (ref "R21") (pin "1") (pintype "passive"))
      (node (ref "U4") (pin "14") (pinfunction "RXLED_14") (pintype "passive"))
    )
    (net (code "106") (name "Net-(U4-TXD)") (class "Default")
      (node (ref "R14") (pin "1") (pintype "passive"))
      (node (ref "U4") (pin "1") (pinfunction "TXD_1") (pintype "passive"))
    )
    (net (code "107") (name "Net-(U4-TXLED)") (class "Default")
      (node (ref "R20") (pin "1") (pintype "passive"))
      (node (ref "U4") (pin "7") (pinfunction "TXLED_7") (pintype "passive"))
    )
    (net (code "108") (name "Net-(U4-USBD+)") (class "Default")
      (node (ref "R17") (pin "2") (pintype "passive"))
      (node (ref "U4") (pin "8") (pinfunction "USBD+_8") (pintype "passive"))
    )
    (net (code "109") (name "Net-(U4-USBD-)") (class "Default")
      (node (ref "R16") (pin "2") (pintype "passive"))
      (node (ref "U4") (pin "9") (pinfunction "USBD-_9") (pintype "passive"))
    )
    (net (code "110") (name "unconnected-(H1-ADC_IN0-Pad7)") (class "Default")
      (node (ref "H1") (pin "7") (pinfunction "ADC_IN0_7") (pintype "passive"))
    )
    (net (code "111") (name "unconnected-(H1-ADC_IN1-Pad8)") (class "Default")
      (node (ref "H1") (pin "8") (pinfunction "ADC_IN1_8") (pintype "passive"))
    )
    (net (code "112") (name "unconnected-(H1-ADC_IN2-Pad9)") (class "Default")
      (node (ref "H1") (pin "9") (pinfunction "ADC_IN2_9") (pintype "passive"))
    )
    (net (code "113") (name "unconnected-(H1-ADC_IN3-Pad10)") (class "Default")
      (node (ref "H1") (pin "10") (pinfunction "ADC_IN3_10") (pintype "passive"))
    )
    (net (code "114") (name "unconnected-(H1-RESET-Pad16)") (class "Default")
      (node (ref "H1") (pin "16") (pinfunction "RESET_16") (pintype "passive"))
    )
    (net (code "115") (name "unconnected-(H1-UART0_CTS-Pad4)") (class "Default")
      (node (ref "H1") (pin "4") (pinfunction "UART0_CTS_4") (pintype "passive"))
    )
    (net (code "116") (name "unconnected-(H1-UART0_RTS-Pad3)") (class "Default")
      (node (ref "H1") (pin "3") (pinfunction "UART0_RTS_3") (pintype "passive"))
    )
    (net (code "117") (name "unconnected-(H1-UART1_RX-Pad12)") (class "Default")
      (node (ref "H1") (pin "12") (pinfunction "UART1_RX_12") (pintype "passive"))
    )
    (net (code "118") (name "unconnected-(H1-UART1_TX-Pad13)") (class "Default")
      (node (ref "H1") (pin "13") (pinfunction "UART1_TX_13") (pintype "passive"))
    )
    (net (code "119") (name "unconnected-(H1-UART2_RX-Pad15)") (class "Default")
      (node (ref "H1") (pin "15") (pinfunction "UART2_RX_15") (pintype "passive"))
    )
    (net (code "120") (name "unconnected-(H1-UART2_TX-Pad14)") (class "Default")
      (node (ref "H1") (pin "14") (pinfunction "UART2_TX_14") (pintype "passive"))
    )
    (net (code "121") (name "unconnected-(H2-NC-Pad6)") (class "Default")
      (node (ref "H2") (pin "6") (pinfunction "NC_6") (pintype "passive"))
    )
    (net (code "122") (name "unconnected-(H2-TRST-Pad2)") (class "Default")
      (node (ref "H2") (pin "2") (pinfunction "TRST_2") (pintype "passive"))
    )
    (net (code "123") (name "unconnected-(J1-PWR_BAT-Pad3)") (class "Default")
      (node (ref "J1") (pin "3") (pinfunction "PWR_BAT_3") (pintype "passive"))
    )
    (net (code "124") (name "unconnected-(U1-BST-Pad11)") (class "Default")
      (node (ref "U1") (pin "11") (pinfunction "BST_11") (pintype "passive"))
    )
    (net (code "125") (name "unconnected-(U1-NC-Pad10)") (class "Default")
      (node (ref "U1") (pin "10") (pinfunction "NC_10") (pintype "passive"))
    )
    (net (code "126") (name "unconnected-(U1-NC-Pad15)") (class "Default")
      (node (ref "U1") (pin "15") (pinfunction "NC_15") (pintype "passive"))
    )
    (net (code "127") (name "unconnected-(U1-SW-Pad4)") (class "Default")
      (node (ref "U1") (pin "4") (pinfunction "SW_4") (pintype "passive"))
    )
    (net (code "128") (name "unconnected-(U1-VCC-Pad2)") (class "Default")
      (node (ref "U1") (pin "2") (pinfunction "VCC_2") (pintype "passive"))
    )
    (net (code "129") (name "unconnected-(U2-A0{slash}C15-Pad11)") (class "Default")
      (node (ref "U2") (pin "11") (pinfunction "A0/C15_11") (pintype "passive"))
    )
    (net (code "130") (name "unconnected-(U2-A1-Pad10)") (class "Default")
      (node (ref "U2") (pin "10") (pinfunction "A1_10") (pintype "passive"))
    )
    (net (code "131") (name "unconnected-(U2-A11{slash}C0-Pad8)") (class "Default")
      (node (ref "U2") (pin "8") (pinfunction "A11/C0_8") (pintype "passive"))
    )
    (net (code "132") (name "unconnected-(U3-BST-Pad11)") (class "Default")
      (node (ref "U3") (pin "11") (pinfunction "BST_11") (pintype "passive"))
    )
    (net (code "133") (name "unconnected-(U3-NC-Pad10)") (class "Default")
      (node (ref "U3") (pin "10") (pinfunction "NC_10") (pintype "passive"))
    )
    (net (code "134") (name "unconnected-(U3-NC-Pad15)") (class "Default")
      (node (ref "U3") (pin "15") (pinfunction "NC_15") (pintype "passive"))
    )
    (net (code "135") (name "unconnected-(U3-SW-Pad4)") (class "Default")
      (node (ref "U3") (pin "4") (pinfunction "SW_4") (pintype "passive"))
    )
    (net (code "136") (name "unconnected-(U3-VCC-Pad2)") (class "Default")
      (node (ref "U3") (pin "2") (pinfunction "VCC_2") (pintype "passive"))
    )
    (net (code "137") (name "unconnected-(U4-CTS-Pad6)") (class "Default")
      (node (ref "U4") (pin "6") (pinfunction "CTS_6") (pintype "passive"))
    )
    (net (code "138") (name "unconnected-(U4-IO2-Pad16)") (class "Default")
      (node (ref "U4") (pin "16") (pinfunction "IO2_16") (pintype "passive"))
    )
    (net (code "139") (name "unconnected-(U4-RTS-Pad2)") (class "Default")
      (node (ref "U4") (pin "2") (pinfunction "RTS_2") (pintype "passive"))
    )
    (net (code "140") (name "unconnected-(U5-NC-Pad4)") (class "Default")
      (node (ref "U5") (pin "4") (pinfunction "NC_4") (pintype "passive"))
    )
  )
)
